# DS136-1_0.net
KiCad netlist of a schematic drawn in Altium Designer
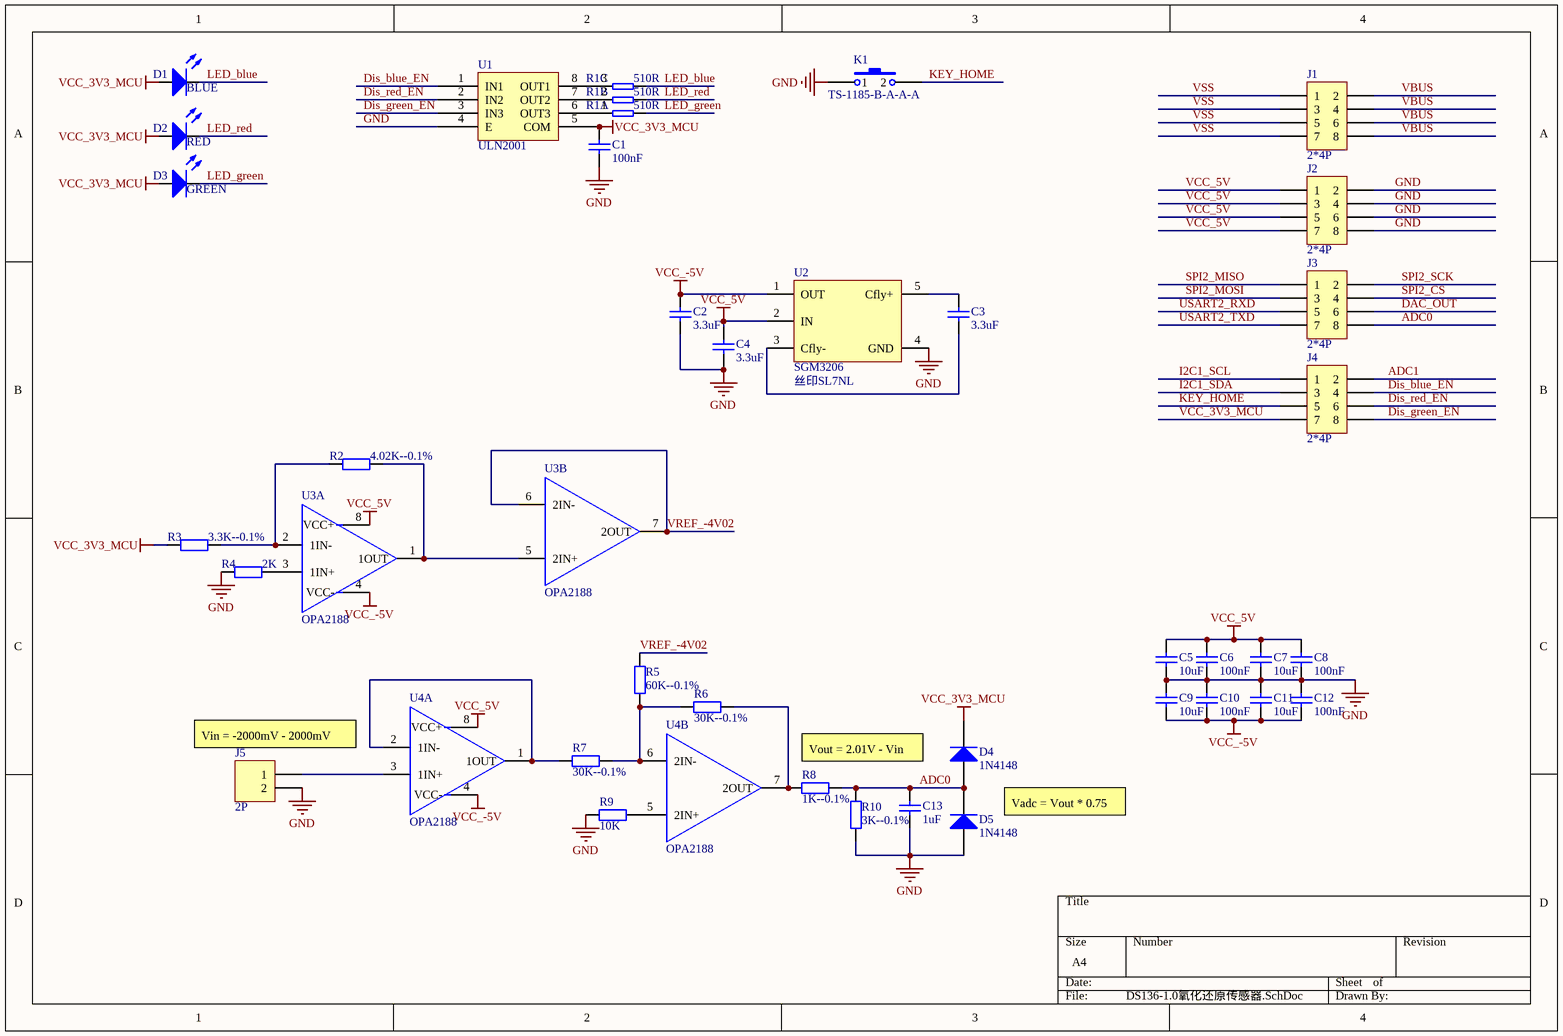
[diagram p0: DS136-1.0氧化还原传感器.SchDoc]

(export (version "E")
  (design (tool "Eeschema 10.0.6"))
  (components
    (comp (ref "C1")
      (value "100nF")
      (footprint "0603CAP")
      (description "贴片电容")
      (fields (field (name "Comment") "SMDCAP00013"))
      (libsource (lib "AD_SCH") (part "MLCC 100nF 50V ±10％ 0603"))
    )
    (comp (ref "C2")
      (value "3.3uF")
      (footprint "0603CAP")
      (description "贴片电容")
      (fields (field (name "Comment") "SMDCAP00013"))
      (libsource (lib "AD_SCH") (part "MLCC 100nF 50V ±10％ 0603"))
    )
    (comp (ref "C3")
      (value "3.3uF")
      (footprint "0603CAP")
      (description "贴片电容")
      (fields (field (name "Comment") "SMDCAP00013"))
      (libsource (lib "AD_SCH") (part "MLCC 100nF 50V ±10％ 0603"))
    )
    (comp (ref "C4")
      (value "3.3uF")
      (footprint "0603CAP")
      (description "贴片电容")
      (fields (field (name "Comment") "SMDCAP00013"))
      (libsource (lib "AD_SCH") (part "MLCC 100nF 50V ±10％ 0603"))
    )
    (comp (ref "C5")
      (value "10uF")
      (footprint "0603CAP")
      (description "贴片电容")
      (fields (field (name "Comment") "SMDCAP00016"))
      (libsource (lib "AD_SCH") (part "MLCC 10uF 50V ±10％ 0603"))
    )
    (comp (ref "C6")
      (value "100nF")
      (footprint "0603CAP")
      (description "贴片电容")
      (fields (field (name "Comment") "SMDCAP00013"))
      (libsource (lib "AD_SCH") (part "MLCC 100nF 50V ±10％ 0603"))
    )
    (comp (ref "C7")
      (value "10uF")
      (footprint "0603CAP")
      (description "贴片电容")
      (fields (field (name "Comment") "SMDCAP00016"))
      (libsource (lib "AD_SCH") (part "MLCC 10uF 50V ±10％ 0603"))
    )
    (comp (ref "C8")
      (value "100nF")
      (footprint "0603CAP")
      (description "贴片电容")
      (fields (field (name "Comment") "SMDCAP00013"))
      (libsource (lib "AD_SCH") (part "MLCC 100nF 50V ±10％ 0603"))
    )
    (comp (ref "C9")
      (value "10uF")
      (footprint "0603CAP")
      (description "贴片电容")
      (fields (field (name "Comment") "SMDCAP00016"))
      (libsource (lib "AD_SCH") (part "MLCC 10uF 50V ±10％ 0603"))
    )
    (comp (ref "C10")
      (value "100nF")
      (footprint "0603CAP")
      (description "贴片电容")
      (fields (field (name "Comment") "SMDCAP00013"))
      (libsource (lib "AD_SCH") (part "MLCC 100nF 50V ±10％ 0603"))
    )
    (comp (ref "C11")
      (value "10uF")
      (footprint "0603CAP")
      (description "贴片电容")
      (fields (field (name "Comment") "SMDCAP00016"))
      (libsource (lib "AD_SCH") (part "MLCC 10uF 50V ±10％ 0603"))
    )
    (comp (ref "C12")
      (value "100nF")
      (footprint "0603CAP")
      (description "贴片电容")
      (fields (field (name "Comment") "SMDCAP00013"))
      (libsource (lib "AD_SCH") (part "MLCC 100nF 50V ±10％ 0603"))
    )
    (comp (ref "C13")
      (value "1uF")
      (footprint "0603CAP")
      (description "贴片电容")
      (fields (field (name "Comment") "SMDCAP00015"))
      (libsource (lib "AD_SCH") (part "MLCC 1uF 50V ±10％ 0603"))
    )
    (comp (ref "D1")
      (value "BLUE")
      (footprint "LED_0805")
      (description "贴片LED")
      (fields (field (name "Comment") "SMDLED00010"))
      (libsource (lib "AD_SCH") (part "Chip 蓝色LED 0805"))
    )
    (comp (ref "D2")
      (value "RED")
      (footprint "LED_0805")
      (description "贴片LED")
      (fields (field (name "Comment") "SMDLED00003"))
      (libsource (lib "AD_SCH") (part "Chip 红色LED 0805"))
    )
    (comp (ref "D3")
      (value "GREEN")
      (footprint "LED_0805")
      (description "贴片LED")
      (fields (field (name "Comment") "Chip 翠绿LED 0805"))
      (libsource (lib "AD_SCH") (part "Chip 翠绿LED 0805"))
    )
    (comp (ref "D4")
      (value "1N4148")
      (footprint "LL-34")
      (description "贴片二极管")
      (fields (field (name "Comment") "SMDDIODE02001"))
      (libsource (lib "AD_SCH") (part "玻封 1/2W 1N4148 LL-34"))
    )
    (comp (ref "D5")
      (value "1N4148")
      (footprint "LL-34")
      (description "贴片二极管")
      (fields (field (name "Comment") "SMDDIODE02001"))
      (libsource (lib "AD_SCH") (part "玻封 1/2W 1N4148 LL-34"))
    )
    (comp (ref "J1")
      (value "2*4P")
      (footprint "X1321WVS-2x04J-C40D53")
      (description "双排针2x4P 立贴 1.27mm")
      (fields (field (name "Comment") "X1321WVS-2x04J-C40D53"))
      (libsource (lib "AD_SCH") (part "X1321WVS-2x04J-C40D53"))
    )
    (comp (ref "J2")
      (value "2*4P")
      (footprint "X1321WVS-2x04J-C40D53")
      (description "双排针2x4P 立贴 1.27mm")
      (fields (field (name "Comment") "X1321WVS-2x04J-C40D53"))
      (libsource (lib "AD_SCH") (part "X1321WVS-2x04J-C40D53"))
    )
    (comp (ref "J3")
      (value "2*4P")
      (footprint "X1321WVS-2x04J-C40D53")
      (description "双排针2x4P 立贴 1.27mm")
      (fields (field (name "Comment") "X1321WVS-2x04J-C40D53"))
      (libsource (lib "AD_SCH") (part "X1321WVS-2x04J-C40D53"))
    )
    (comp (ref "J4")
      (value "2*4P")
      (footprint "X1321WVS-2x04J-C40D53")
      (description "双排针2x4P 立贴 1.27mm")
      (fields (field (name "Comment") "X1321WVS-2x04J-C40D53"))
      (libsource (lib "AD_SCH") (part "X1321WVS-2x04J-C40D53"))
    )
    (comp (ref "J5")
      (value "2P")
      (footprint "SIP2")
      (description "单排直针")
      (fields (field (name "Comment") "SL000000042"))
      (libsource (lib "AD_SCH") (part "DIP2 单排直针 1*40P 间距2.54mm 针长11mm 铜"))
    )
    (comp (ref "K1")
      (value "TS-1185-B-A-A-A")
      (footprint "KEY_TS-1185-x-A-A-A")
      (description "轻触开关")
      (libsource (lib "AD_SCH") (part "TS-1185-B-A-A-A"))
    )
    (comp (ref "R1")
      (value "510R")
      (footprint "0603RES_Pack4")
      (description "贴片排阻")
      (fields (field (name "Comment") "SMDRES05003"))
      (libsource (lib "AD_SCH") (part "Chip R*4 510R 1/16W ±5％ 0603"))
    )
    (comp (ref "R2")
      (value "4.02K--0.1%")
      (footprint "0603RES")
      (description "贴片电阻")
      (fields (field (name "Comment") "SMDRES00060"))
      (libsource (lib "") (part "Chip 30K 1/16W ±1％ 0603_1"))
    )
    (comp (ref "R3")
      (value "3.3K--0.1%")
      (footprint "0603RES")
      (description "贴片电阻")
      (fields (field (name "Comment") "SMDRES00090"))
      (libsource (lib "AD_SCH") (part "Chip 3.3K 1/16W ±1％ 0603"))
    )
    (comp (ref "R4")
      (value "2K")
      (footprint "0603RES")
      (description "贴片电阻")
      (fields (field (name "Comment") "SMDRES00042"))
      (libsource (lib "AD_SCH") (part "Chip 2K 1/16W ±1％ 0603"))
    )
    (comp (ref "R5")
      (value "60K--0.1%")
      (footprint "0603RES")
      (description "贴片电阻")
      (fields (field (name "Comment") "SMDRES00060"))
      (libsource (lib "") (part "Chip 30K 1/16W ±1％ 0603_2"))
    )
    (comp (ref "R6")
      (value "30K--0.1%")
      (footprint "0603RES")
      (description "贴片电阻")
      (fields (field (name "Comment") "SMDRES00060"))
      (libsource (lib "AD_SCH") (part "Chip 30K 1/16W ±1％ 0603"))
    )
    (comp (ref "R7")
      (value "30K--0.1%")
      (footprint "0603RES")
      (description "贴片电阻")
      (fields (field (name "Comment") "SMDRES00060"))
      (libsource (lib "AD_SCH") (part "Chip 30K 1/16W ±1％ 0603"))
    )
    (comp (ref "R8")
      (value "1K--0.1%")
      (footprint "0603RES")
      (description "贴片电阻")
      (fields (field (name "Comment") "SMDRES00034"))
      (libsource (lib "AD_SCH") (part "Chip 1K 1/16W ±1％ 0603"))
    )
    (comp (ref "R9")
      (value "10K")
      (footprint "0603RES")
      (description "贴片电阻")
      (fields (field (name "Comment") "SMDRES00056"))
      (libsource (lib "AD_SCH") (part "Chip 10K 1/16W ±1％ 0603"))
    )
    (comp (ref "R10")
      (value "3K--0.1%")
      (footprint "0603RES")
      (description "贴片电阻")
      (fields (field (name "Comment") "Chip 3K 1/16W ±1％ 0603"))
      (libsource (lib "AD_SCH") (part "Chip 3K 1/16W ±1％ 0603"))
    )
    (comp (ref "U1")
      (value "ULN2001")
      (footprint "SO-8")
      (description "电机驱动芯片")
      (fields (field (name "Comment") "SMDIC000018"))
      (libsource (lib "AD_SCH") (part "ULN2001 SOP-8"))
    )
    (comp (ref "U2")
      (value "SGM3206")
      (footprint "SOT23-5")
      (description "电荷泵芯片")
      (fields (field (name "ALTIUM_VALUE") "丝印SL7NL"))
      (libsource (lib "AD_SCH") (part "SGM3206"))
    )
    (comp (ref "U3") (value "OPA2188") (footprint "SO-8") (libsource (lib "AD_SCH") (part "TL062C")))
    (comp (ref "U4") (value "OPA2188") (footprint "SO-8") (libsource (lib "AD_SCH") (part "TL062C")))
  )
  (nets
    (net (code "1") (name "/ADC0") (class "Default")
      (node (ref "C13") (pin "2") (pinfunction "2_2") (pintype "passive"))
      (node (ref "D4") (pin "1") (pinfunction "A_1") (pintype "passive"))
      (node (ref "D5") (pin "2") (pinfunction "K_2") (pintype "passive"))
      (node (ref "J3") (pin "8") (pinfunction "8_8") (pintype "passive"))
      (node (ref "R10") (pin "2") (pinfunction "2_2") (pintype "passive"))
      (node (ref "R8") (pin "2") (pinfunction "2_2") (pintype "passive"))
    )
    (net (code "2") (name "/ADC1") (class "Default")
      (node (ref "J4") (pin "2") (pinfunction "2_2") (pintype "passive"))
    )
    (net (code "3") (name "/DAC_OUT") (class "Default")
      (node (ref "J3") (pin "6") (pinfunction "6_6") (pintype "passive"))
    )
    (net (code "4") (name "/Dis_blue_EN") (class "Default")
      (node (ref "J4") (pin "4") (pinfunction "4_4") (pintype "passive"))
      (node (ref "U1") (pin "1") (pinfunction "IN1_1") (pintype "passive"))
    )
    (net (code "5") (name "/Dis_green_EN") (class "Default")
      (node (ref "J4") (pin "8") (pinfunction "8_8") (pintype "passive"))
      (node (ref "U1") (pin "3") (pinfunction "IN3_3") (pintype "passive"))
    )
    (net (code "6") (name "/Dis_red_EN") (class "Default")
      (node (ref "J4") (pin "6") (pinfunction "6_6") (pintype "passive"))
      (node (ref "U1") (pin "2") (pinfunction "IN2_2") (pintype "passive"))
    )
    (net (code "7") (name "/I2C1_SCL") (class "Default")
      (node (ref "J4") (pin "1") (pinfunction "1_1") (pintype "passive"))
    )
    (net (code "8") (name "/I2C1_SDA") (class "Default")
      (node (ref "J4") (pin "3") (pinfunction "3_3") (pintype "passive"))
    )
    (net (code "9") (name "/KEY_HOME") (class "Default")
      (node (ref "J4") (pin "5") (pinfunction "5_5") (pintype "passive"))
      (node (ref "K1") (pin "2") (pinfunction "2_2") (pintype "passive"))
    )
    (net (code "10") (name "/LED_blue") (class "Default")
      (node (ref "D1") (pin "2") (pinfunction "K_2") (pintype "passive"))
      (node (ref "R1") (pin "6") (pinfunction "6_6") (pintype "passive"))
    )
    (net (code "11") (name "/LED_green") (class "Default")
      (node (ref "D3") (pin "2") (pinfunction "K_2") (pintype "passive"))
      (node (ref "R1") (pin "8") (pinfunction "8_8") (pintype "passive"))
    )
    (net (code "12") (name "/LED_red") (class "Default")
      (node (ref "D2") (pin "2") (pinfunction "K_2") (pintype "passive"))
      (node (ref "R1") (pin "7") (pinfunction "7_7") (pintype "passive"))
    )
    (net (code "13") (name "/SPI2_CS") (class "Default")
      (node (ref "J3") (pin "4") (pinfunction "4_4") (pintype "passive"))
    )
    (net (code "14") (name "/SPI2_MISO") (class "Default")
      (node (ref "J3") (pin "1") (pinfunction "1_1") (pintype "passive"))
    )
    (net (code "15") (name "/SPI2_MOSI") (class "Default")
      (node (ref "J3") (pin "3") (pinfunction "3_3") (pintype "passive"))
    )
    (net (code "16") (name "/SPI2_SCK") (class "Default")
      (node (ref "J3") (pin "2") (pinfunction "2_2") (pintype "passive"))
    )
    (net (code "17") (name "/USART2_RXD") (class "Default")
      (node (ref "J3") (pin "5") (pinfunction "5_5") (pintype "passive"))
    )
    (net (code "18") (name "/USART2_TXD") (class "Default")
      (node (ref "J3") (pin "7") (pinfunction "7_7") (pintype "passive"))
    )
    (net (code "19") (name "/VBUS") (class "Default")
      (node (ref "J1") (pin "2") (pinfunction "2_2") (pintype "passive"))
      (node (ref "J1") (pin "4") (pinfunction "4_4") (pintype "passive"))
      (node (ref "J1") (pin "6") (pinfunction "6_6") (pintype "passive"))
      (node (ref "J1") (pin "8") (pinfunction "8_8") (pintype "passive"))
    )
    (net (code "20") (name "/VREF_-4V02") (class "Default")
      (node (ref "R5") (pin "2") (pinfunction "2_2") (pintype "passive"))
      (node (ref "U3") (pin "6") (pinfunction "2IN-_6") (pintype "passive"))
      (node (ref "U3") (pin "7") (pinfunction "2OUT_7") (pintype "passive"))
    )
    (net (code "21") (name "/VSS") (class "Default")
      (node (ref "J1") (pin "1") (pinfunction "1_1") (pintype "passive"))
      (node (ref "J1") (pin "3") (pinfunction "3_3") (pintype "passive"))
      (node (ref "J1") (pin "5") (pinfunction "5_5") (pintype "passive"))
      (node (ref "J1") (pin "7") (pinfunction "7_7") (pintype "passive"))
    )
    (net (code "22") (name "GND") (class "Default")
      (node (ref "C1") (pin "1") (pinfunction "1_1") (pintype "passive"))
      (node (ref "C10") (pin "2") (pinfunction "2_2") (pintype "passive"))
      (node (ref "C11") (pin "2") (pinfunction "2_2") (pintype "passive"))
      (node (ref "C12") (pin "2") (pinfunction "2_2") (pintype "passive"))
      (node (ref "C13") (pin "1") (pinfunction "1_1") (pintype "passive"))
      (node (ref "C2") (pin "1") (pinfunction "1_1") (pintype "passive"))
      (node (ref "C4") (pin "2") (pinfunction "2_2") (pintype "passive"))
      (node (ref "C5") (pin "1") (pinfunction "1_1") (pintype "passive"))
      (node (ref "C6") (pin "1") (pinfunction "1_1") (pintype "passive"))
      (node (ref "C7") (pin "1") (pinfunction "1_1") (pintype "passive"))
      (node (ref "C8") (pin "1") (pinfunction "1_1") (pintype "passive"))
      (node (ref "C9") (pin "2") (pinfunction "2_2") (pintype "passive"))
      (node (ref "D5") (pin "1") (pinfunction "A_1") (pintype "passive"))
      (node (ref "J2") (pin "2") (pinfunction "2_2") (pintype "passive"))
      (node (ref "J2") (pin "4") (pinfunction "4_4") (pintype "passive"))
      (node (ref "J2") (pin "6") (pinfunction "6_6") (pintype "passive"))
      (node (ref "J2") (pin "8") (pinfunction "8_8") (pintype "passive"))
      (node (ref "J5") (pin "2") (pinfunction "2_2") (pintype "passive"))
      (node (ref "K1") (pin "1") (pinfunction "1_1") (pintype "passive"))
      (node (ref "R10") (pin "1") (pinfunction "1_1") (pintype "passive"))
      (node (ref "R4") (pin "1") (pinfunction "1_1") (pintype "passive"))
      (node (ref "R9") (pin "1") (pinfunction "1_1") (pintype "passive"))
      (node (ref "U1") (pin "4") (pinfunction "E_4") (pintype "passive"))
      (node (ref "U2") (pin "4") (pinfunction "GND_4") (pintype "passive"))
    )
    (net (code "23") (name "Net-(U1-OUT1)") (class "Default")
      (node (ref "R1") (pin "3") (pinfunction "3_3") (pintype "passive"))
      (node (ref "U1") (pin "8") (pinfunction "OUT1_8") (pintype "passive"))
    )
    (net (code "24") (name "Net-(U1-OUT2)") (class "Default")
      (node (ref "R1") (pin "2") (pinfunction "2_2") (pintype "passive"))
      (node (ref "U1") (pin "7") (pinfunction "OUT2_7") (pintype "passive"))
    )
    (net (code "25") (name "Net-(U1-OUT3)") (class "Default")
      (node (ref "R1") (pin "1") (pinfunction "1_1") (pintype "passive"))
      (node (ref "U1") (pin "6") (pinfunction "OUT3_6") (pintype "passive"))
    )
    (net (code "26") (name "Net-(U2-Cfly+)") (class "Default")
      (node (ref "C3") (pin "1") (pinfunction "1_1") (pintype "passive"))
      (node (ref "U2") (pin "5") (pinfunction "Cfly+_5") (pintype "passive"))
    )
    (net (code "27") (name "Net-(U2-Cfly-)") (class "Default")
      (node (ref "C3") (pin "2") (pinfunction "2_2") (pintype "passive"))
      (node (ref "U2") (pin "3") (pinfunction "Cfly-_3") (pintype "passive"))
    )
    (net (code "28") (name "Net-(U3A-1IN+)") (class "Default")
      (node (ref "R4") (pin "2") (pinfunction "2_2") (pintype "passive"))
      (node (ref "U3") (pin "3") (pinfunction "1IN+_3") (pintype "passive"))
    )
    (net (code "29") (name "Net-(U3A-1IN-)") (class "Default")
      (node (ref "R2") (pin "2") (pinfunction "2_2") (pintype "passive"))
      (node (ref "R3") (pin "1") (pinfunction "1_1") (pintype "passive"))
      (node (ref "U3") (pin "2") (pinfunction "1IN-_2") (pintype "passive"))
    )
    (net (code "30") (name "Net-(U3A-1OUT)") (class "Default")
      (node (ref "R2") (pin "1") (pinfunction "1_1") (pintype "passive"))
      (node (ref "U3") (pin "1") (pinfunction "1OUT_1") (pintype "passive"))
      (node (ref "U3") (pin "5") (pinfunction "2IN+_5") (pintype "passive"))
    )
    (net (code "31") (name "Net-(U4A-1IN+)") (class "Default")
      (node (ref "J5") (pin "1") (pinfunction "1_1") (pintype "passive"))
      (node (ref "U4") (pin "3") (pinfunction "1IN+_3") (pintype "passive"))
    )
    (net (code "32") (name "Net-(U4A-1IN-)") (class "Default")
      (node (ref "R7") (pin "1") (pinfunction "1_1") (pintype "passive"))
      (node (ref "U4") (pin "1") (pinfunction "1OUT_1") (pintype "passive"))
      (node (ref "U4") (pin "2") (pinfunction "1IN-_2") (pintype "passive"))
    )
    (net (code "33") (name "Net-(U4B-2IN+)") (class "Default")
      (node (ref "R9") (pin "2") (pinfunction "2_2") (pintype "passive"))
      (node (ref "U4") (pin "5") (pinfunction "2IN+_5") (pintype "passive"))
    )
    (net (code "34") (name "Net-(U4B-2IN-)") (class "Default")
      (node (ref "R5") (pin "1") (pinfunction "1_1") (pintype "passive"))
      (node (ref "R6") (pin "1") (pinfunction "1_1") (pintype "passive"))
      (node (ref "R7") (pin "2") (pinfunction "2_2") (pintype "passive"))
      (node (ref "U4") (pin "6") (pinfunction "2IN-_6") (pintype "passive"))
    )
    (net (code "35") (name "Net-(U4B-2OUT)") (class "Default")
      (node (ref "R6") (pin "2") (pinfunction "2_2") (pintype "passive"))
      (node (ref "R8") (pin "1") (pinfunction "1_1") (pintype "passive"))
      (node (ref "U4") (pin "7") (pinfunction "2OUT_7") (pintype "passive"))
    )
    (net (code "36") (name "VCC_-5V") (class "Default")
      (node (ref "C10") (pin "1") (pinfunction "1_1") (pintype "passive"))
      (node (ref "C11") (pin "1") (pinfunction "1_1") (pintype "passive"))
      (node (ref "C12") (pin "1") (pinfunction "1_1") (pintype "passive"))
      (node (ref "C2") (pin "2") (pinfunction "2_2") (pintype "passive"))
      (node (ref "C9") (pin "1") (pinfunction "1_1") (pintype "passive"))
      (node (ref "U2") (pin "1") (pinfunction "OUT_1") (pintype "passive"))
      (node (ref "U3") (pin "4") (pinfunction "VCC-_4") (pintype "passive"))
      (node (ref "U4") (pin "4") (pinfunction "VCC-_4") (pintype "passive"))
    )
    (net (code "37") (name "VCC_3V3_MCU") (class "Default")
      (node (ref "C1") (pin "2") (pinfunction "2_2") (pintype "passive"))
      (node (ref "D1") (pin "1") (pinfunction "A_1") (pintype "passive"))
      (node (ref "D2") (pin "1") (pinfunction "A_1") (pintype "passive"))
      (node (ref "D3") (pin "1") (pinfunction "A_1") (pintype "passive"))
      (node (ref "D4") (pin "2") (pinfunction "K_2") (pintype "passive"))
      (node (ref "J4") (pin "7") (pinfunction "7_7") (pintype "passive"))
      (node (ref "R3") (pin "2") (pinfunction "2_2") (pintype "passive"))
      (node (ref "U1") (pin "5") (pinfunction "COM_5") (pintype "passive"))
    )
    (net (code "38") (name "VCC_5V") (class "Default")
      (node (ref "C4") (pin "1") (pinfunction "1_1") (pintype "passive"))
      (node (ref "C5") (pin "2") (pinfunction "2_2") (pintype "passive"))
      (node (ref "C6") (pin "2") (pinfunction "2_2") (pintype "passive"))
      (node (ref "C7") (pin "2") (pinfunction "2_2") (pintype "passive"))
      (node (ref "C8") (pin "2") (pinfunction "2_2") (pintype "passive"))
      (node (ref "J2") (pin "1") (pinfunction "1_1") (pintype "passive"))
      (node (ref "J2") (pin "3") (pinfunction "3_3") (pintype "passive"))
      (node (ref "J2") (pin "5") (pinfunction "5_5") (pintype "passive"))
      (node (ref "J2") (pin "7") (pinfunction "7_7") (pintype "passive"))
      (node (ref "U2") (pin "2") (pinfunction "IN_2") (pintype "passive"))
      (node (ref "U3") (pin "8") (pinfunction "VCC+_8") (pintype "passive"))
      (node (ref "U4") (pin "8") (pinfunction "VCC+_8") (pintype "passive"))
    )
  )
)
